# Power.net
KiCad netlist of a schematic drawn in Altium Designer
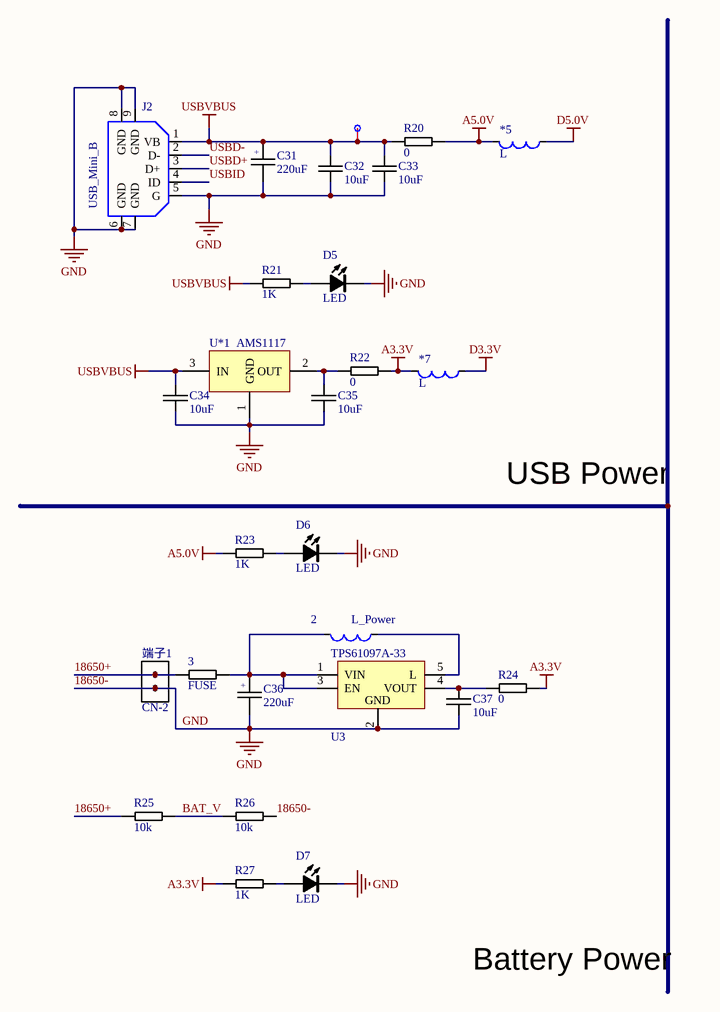
[diagram p0: Power.SchDoc]

(export (version "E")
  (design (tool "Eeschema 10.0.6"))
  (components
    (comp (ref "*5") (value "L") (footprint "0805") (libsource (lib "authuir") (part "L")))
    (comp (ref "*6") (value "Point") (footprint "Point") (libsource (lib "authuir") (part "Point")))
    (comp (ref "*7") (value "L") (footprint "0805") (libsource (lib "authuir") (part "L")))
    (comp (ref "2") (value "L_Power") (footprint "GDSD3316") (libsource (lib "authuir") (part "L_Power")))
    (comp (ref "3") (value "FUSE") (footprint "1812") (libsource (lib "authuir") (part "FUSE")))
    (comp (ref "C31") (value "220uF") (footprint "钽电容7343") (libsource (lib "authuir") (part "钽电容")))
    (comp (ref "C32")
      (value "10uF")
      (footprint "0805-C")
      (description "贴片")
      (libsource (lib "authuir") (part "CAP_Chip"))
    )
    (comp (ref "C33")
      (value "10uF")
      (footprint "0805-C")
      (description "贴片")
      (libsource (lib "authuir") (part "CAP_Chip"))
    )
    (comp (ref "C34")
      (value "10uF")
      (footprint "0805-C")
      (description "贴片")
      (libsource (lib "authuir") (part "CAP_Chip"))
    )
    (comp (ref "C35")
      (value "10uF")
      (footprint "0805-C")
      (description "贴片")
      (libsource (lib "authuir") (part "CAP_Chip"))
    )
    (comp (ref "C36") (value "220uF") (footprint "钽电容7343") (libsource (lib "authuir") (part "钽电容")))
    (comp (ref "C37")
      (value "10uF")
      (footprint "0805-C")
      (description "贴片")
      (libsource (lib "authuir") (part "CAP_Chip"))
    )
    (comp (ref "D5")
      (value "LED")
      (footprint "0805-LED")
      (description "贴片")
      (libsource (lib "authuir") (part "LED"))
    )
    (comp (ref "D6")
      (value "LED")
      (footprint "0805-LED")
      (description "贴片")
      (libsource (lib "authuir") (part "LED"))
    )
    (comp (ref "D7")
      (value "LED")
      (footprint "0805-LED")
      (description "贴片")
      (libsource (lib "authuir") (part "LED"))
    )
    (comp (ref "J2")
      (value "USB_Mini_B")
      (footprint "USB_Mini_B")
      (libsource (lib "authuir") (part "USB_Mini_B"))
    )
    (comp (ref "R20")
      (value "0")
      (footprint "0805-R")
      (description "贴片")
      (libsource (lib "authuir") (part "RES_Chip"))
    )
    (comp (ref "R21")
      (value "1K")
      (footprint "0805-R")
      (description "贴片")
      (libsource (lib "authuir") (part "RES_Chip"))
    )
    (comp (ref "R22")
      (value "0")
      (footprint "0805-R")
      (description "贴片")
      (libsource (lib "authuir") (part "RES_Chip"))
    )
    (comp (ref "R23")
      (value "1K")
      (footprint "0805-R")
      (description "贴片")
      (libsource (lib "authuir") (part "RES_Chip"))
    )
    (comp (ref "R24")
      (value "0")
      (footprint "0805-R")
      (description "贴片")
      (libsource (lib "authuir") (part "RES_Chip"))
    )
    (comp (ref "R25")
      (value "10k")
      (footprint "0603")
      (description "贴片")
      (libsource (lib "authuir") (part "RES_Chip"))
    )
    (comp (ref "R26")
      (value "10k")
      (footprint "0603")
      (description "贴片")
      (libsource (lib "authuir") (part "RES_Chip"))
    )
    (comp (ref "R27")
      (value "1K")
      (footprint "0805-R")
      (description "贴片")
      (libsource (lib "authuir") (part "RES_Chip"))
    )
    (comp (ref "U*1") (value "AMS1117") (footprint "SOT-223") (libsource (lib "authuir") (part "AMS1117")))
    (comp (ref "U3")
      (value "TPS61097A-33")
      (footprint "DBV005_L")
      (libsource (lib "authuir") (part "TPS61097A-33"))
    )
    (comp (ref "端子1") (value "CN-2") (footprint "SIP-2") (libsource (lib "开关·连接器") (part "CN-2")))
  )
  (nets
    (net (code "1") (name "/18650+") (class "Default")
      (node (ref "3") (pin "1") (pinfunction "1_1") (pintype "passive"))
      (node (ref "R25") (pin "1") (pinfunction "1_1") (pintype "passive"))
      (node (ref "端子1") (pin "1") (pinfunction "1_1") (pintype "passive"))
    )
    (net (code "2") (name "/BAT_V") (class "Default")
      (node (ref "R25") (pin "2") (pinfunction "2_2") (pintype "passive"))
      (node (ref "R26") (pin "1") (pinfunction "1_1") (pintype "passive"))
    )
    (net (code "3") (name "/USBD+") (class "Default")
      (node (ref "J2") (pin "3") (pinfunction "D+_3") (pintype "passive"))
    )
    (net (code "4") (name "/USBD-") (class "Default")
      (node (ref "J2") (pin "2") (pinfunction "D-_2") (pintype "passive"))
    )
    (net (code "5") (name "/USBID") (class "Default")
      (node (ref "J2") (pin "4") (pinfunction "ID_4") (pintype "passive"))
    )
    (net (code "6") (name "A3.3V") (class "Default")
      (node (ref "*7") (pin "1") (pinfunction "1_1") (pintype "passive"))
      (node (ref "R22") (pin "2") (pinfunction "2_2") (pintype "passive"))
      (node (ref "R24") (pin "2") (pinfunction "2_2") (pintype "passive"))
      (node (ref "R27") (pin "1") (pinfunction "1_1") (pintype "passive"))
    )
    (net (code "7") (name "A5.0V") (class "Default")
      (node (ref "*5") (pin "1") (pinfunction "1_1") (pintype "passive"))
      (node (ref "R20") (pin "2") (pinfunction "2_2") (pintype "passive"))
      (node (ref "R23") (pin "1") (pinfunction "1_1") (pintype "passive"))
    )
    (net (code "8") (name "D3.3V") (class "Default")
      (node (ref "*7") (pin "2") (pinfunction "2_2") (pintype "passive"))
    )
    (net (code "9") (name "D5.0V") (class "Default")
      (node (ref "*5") (pin "2") (pinfunction "2_2") (pintype "passive"))
    )
    (net (code "10") (name "GND") (class "Default")
      (node (ref "C31") (pin "1") (pinfunction "1_1") (pintype "passive"))
      (node (ref "C32") (pin "2") (pinfunction "2_2") (pintype "passive"))
      (node (ref "C33") (pin "2") (pinfunction "2_2") (pintype "passive"))
      (node (ref "C34") (pin "2") (pinfunction "2_2") (pintype "passive"))
      (node (ref "C35") (pin "2") (pinfunction "2_2") (pintype "passive"))
      (node (ref "C36") (pin "1") (pinfunction "1_1") (pintype "passive"))
      (node (ref "C37") (pin "2") (pinfunction "2_2") (pintype "passive"))
      (node (ref "D5") (pin "2") (pinfunction "K_2") (pintype "passive"))
      (node (ref "D6") (pin "2") (pinfunction "K_2") (pintype "passive"))
      (node (ref "D7") (pin "2") (pinfunction "K_2") (pintype "passive"))
      (node (ref "J2") (pin "5") (pinfunction "G_5") (pintype "passive"))
      (node (ref "J2") (pin "6") (pinfunction "GND_6") (pintype "passive"))
      (node (ref "J2") (pin "7") (pinfunction "GND_7") (pintype "passive"))
      (node (ref "J2") (pin "8") (pinfunction "GND_8") (pintype "passive"))
      (node (ref "J2") (pin "9") (pinfunction "GND_9") (pintype "passive"))
      (node (ref "R26") (pin "2") (pinfunction "2_2") (pintype "passive"))
      (node (ref "U*1") (pin "1") (pinfunction "GND_1") (pintype "passive"))
      (node (ref "U3") (pin "2") (pinfunction "GND_2") (pintype "passive"))
      (node (ref "端子1") (pin "2") (pinfunction "2_2") (pintype "passive"))
    )
    (net (code "11") (name "Net-(D5-A)") (class "Default")
      (node (ref "D5") (pin "1") (pinfunction "A_1") (pintype "passive"))
      (node (ref "R21") (pin "2") (pinfunction "2_2") (pintype "passive"))
    )
    (net (code "12") (name "Net-(D6-A)") (class "Default")
      (node (ref "D6") (pin "1") (pinfunction "A_1") (pintype "passive"))
      (node (ref "R23") (pin "2") (pinfunction "2_2") (pintype "passive"))
    )
    (net (code "13") (name "Net-(D7-A)") (class "Default")
      (node (ref "D7") (pin "1") (pinfunction "A_1") (pintype "passive"))
      (node (ref "R27") (pin "2") (pinfunction "2_2") (pintype "passive"))
    )
    (net (code "14") (name "Net-(U*1-OUT)") (class "Default")
      (node (ref "C35") (pin "1") (pinfunction "1_1") (pintype "passive"))
      (node (ref "R22") (pin "1") (pinfunction "1_1") (pintype "passive"))
      (node (ref "U*1") (pin "2") (pinfunction "OUT_2") (pintype "passive"))
    )
    (net (code "15") (name "Net-(U3-EN)") (class "Default")
      (node (ref "2") (pin "1") (pinfunction "1_1") (pintype "passive"))
      (node (ref "3") (pin "2") (pinfunction "2_2") (pintype "passive"))
      (node (ref "C36") (pin "2") (pinfunction "2_2") (pintype "passive"))
      (node (ref "U3") (pin "1") (pinfunction "VIN_1") (pintype "passive"))
      (node (ref "U3") (pin "3") (pinfunction "EN_3") (pintype "passive"))
    )
    (net (code "16") (name "Net-(U3-L)") (class "Default")
      (node (ref "2") (pin "2") (pinfunction "2_2") (pintype "passive"))
      (node (ref "U3") (pin "5") (pinfunction "L_5") (pintype "passive"))
    )
    (net (code "17") (name "Net-(U3-VOUT)") (class "Default")
      (node (ref "C37") (pin "1") (pinfunction "1_1") (pintype "passive"))
      (node (ref "R24") (pin "1") (pinfunction "1_1") (pintype "passive"))
      (node (ref "U3") (pin "4") (pinfunction "VOUT_4") (pintype "passive"))
    )
    (net (code "18") (name "USBVBUS") (class "Default")
      (node (ref "*6") (pin "1") (pinfunction "Point_1") (pintype "passive"))
      (node (ref "C31") (pin "2") (pinfunction "2_2") (pintype "passive"))
      (node (ref "C32") (pin "1") (pinfunction "1_1") (pintype "passive"))
      (node (ref "C33") (pin "1") (pinfunction "1_1") (pintype "passive"))
      (node (ref "C34") (pin "1") (pinfunction "1_1") (pintype "passive"))
      (node (ref "J2") (pin "1") (pinfunction "VB_1") (pintype "passive"))
      (node (ref "R20") (pin "1") (pinfunction "1_1") (pintype "passive"))
      (node (ref "R21") (pin "1") (pinfunction "1_1") (pintype "passive"))
      (node (ref "U*1") (pin "3") (pinfunction "IN_3") (pintype "passive"))
    )
  )
)
